# board2.net
KiCad netlist of a schematic drawn in EAGLE
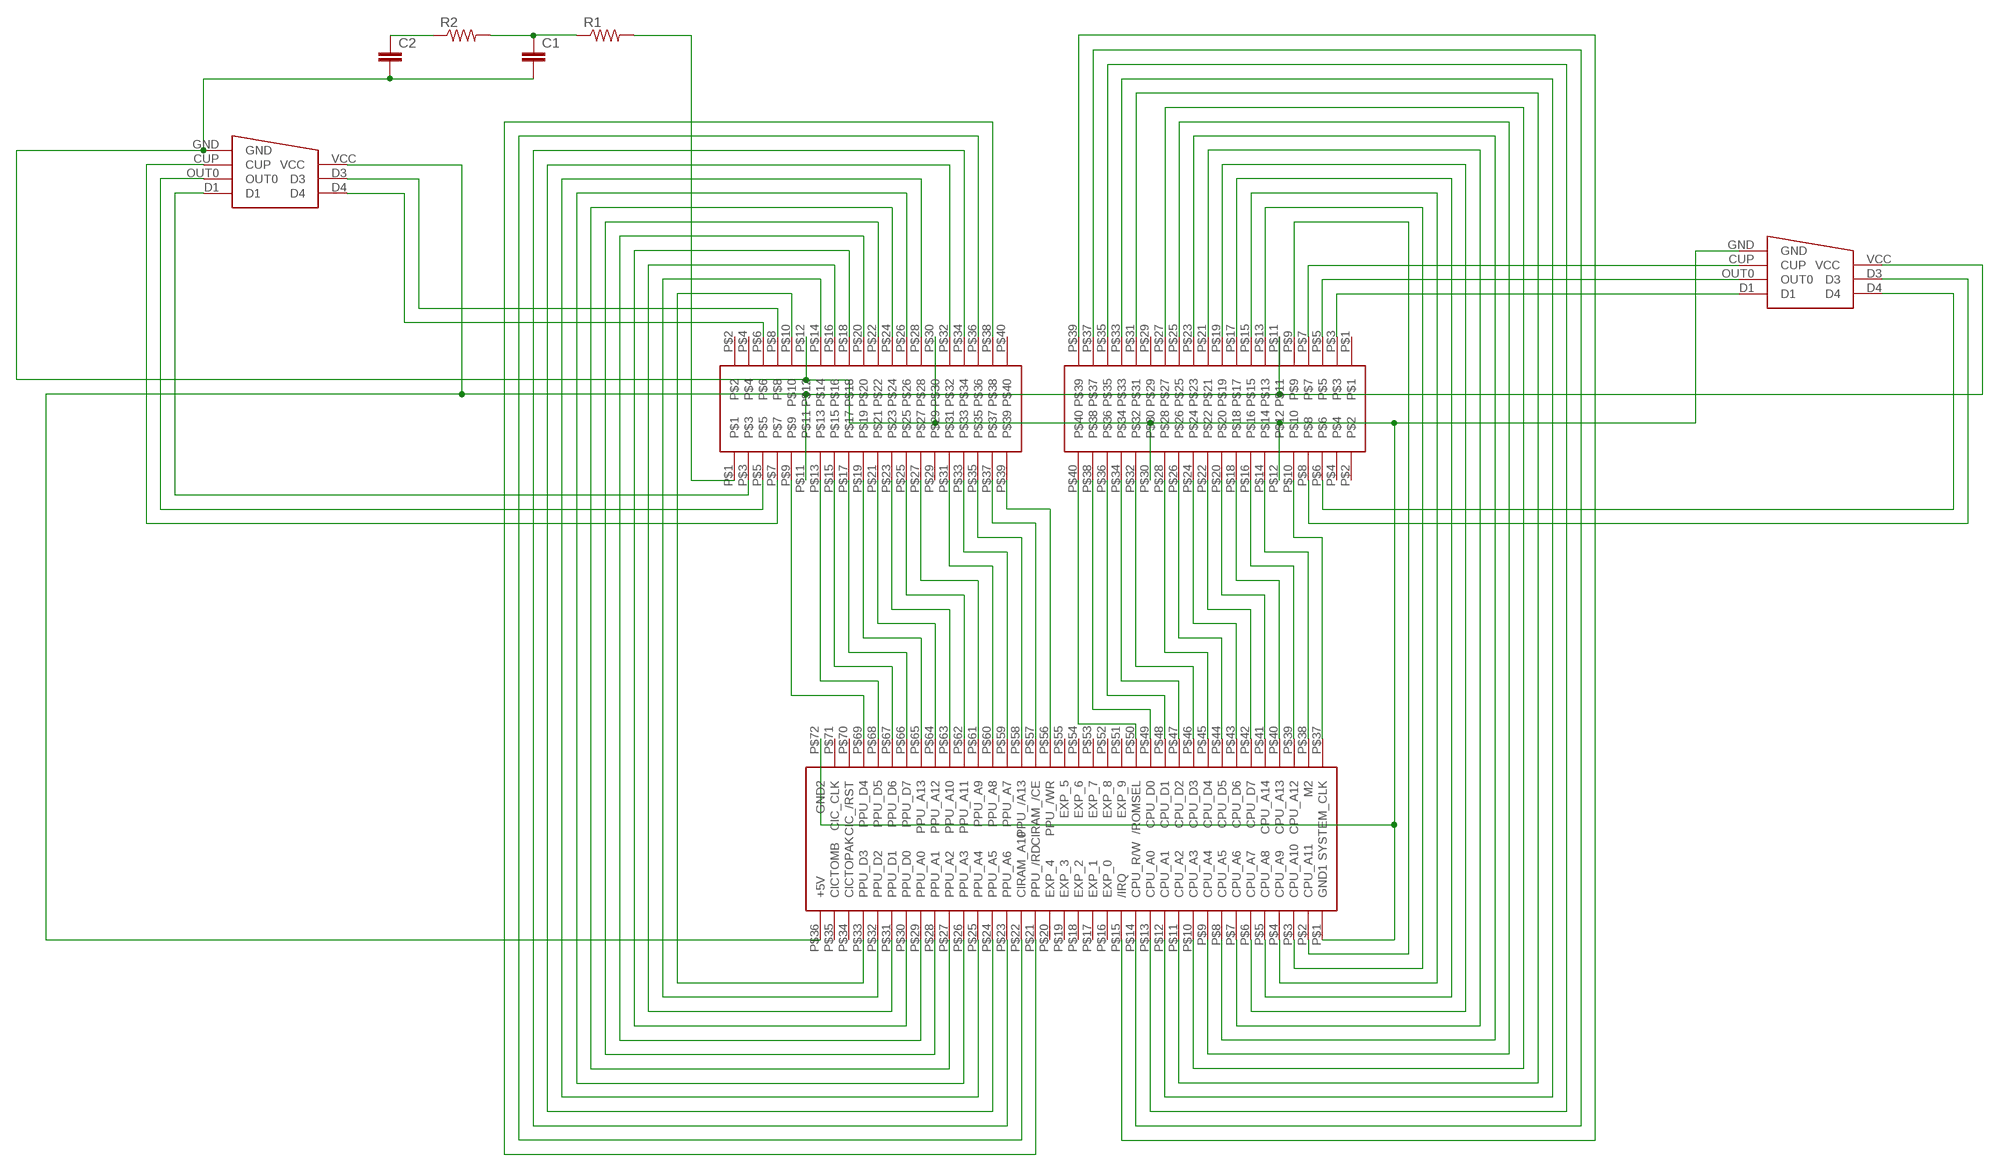
[diagram p0: schematic, sheet 1]

(export (version "E")
  (design (tool "Eeschema 10.0.6"))
  (components
    (comp (ref "C1")
      (value "C5/2.5")
      (footprint "eagle-import:C5B2.5")
      (libsource (lib "eagle-import") (part "C5/2.5"))
    )
    (comp (ref "C2")
      (value "C5/2.5")
      (footprint "eagle-import:C5B2.5")
      (libsource (lib "eagle-import") (part "C5/2.5"))
    )
    (comp (ref "R1")
      (value "R-US_0207/12")
      (footprint "eagle-import:0207_12")
      (libsource (lib "eagle-import") (part "R-US_0207/12"))
    )
    (comp (ref "R2")
      (value "R-US_0207/12")
      (footprint "eagle-import:0207_12")
      (libsource (lib "eagle-import") (part "R-US_0207/12"))
    )
    (comp (ref "U$1")
      (value "NES_CONN")
      (footprint "eagle-import:36X2")
      (libsource (lib "eagle-import") (part "NES_CONN"))
    )
    (comp (ref "U$2")
      (value "40PINNER")
      (footprint "eagle-import:40PINNER")
      (libsource (lib "eagle-import") (part "40PINNER"))
    )
    (comp (ref "U$3")
      (value "40PINNER")
      (footprint "eagle-import:40PINNER")
      (libsource (lib "eagle-import") (part "40PINNER"))
    )
    (comp (ref "U$4")
      (value "7CONN")
      (footprint "eagle-import:7CON")
      (libsource (lib "eagle-import") (part "7CONN"))
    )
    (comp (ref "U$5")
      (value "7CONN")
      (footprint "eagle-import:7CON")
      (libsource (lib "eagle-import") (part "7CONN"))
    )
  )
  (nets
    (net (code "1") (name "Net-(C1-Pad1)") (class "Default")
      (node (ref "C1") (pin "1") (pinfunction "1_1") (pintype "passive"))
      (node (ref "R1") (pin "1") (pinfunction "1_1") (pintype "passive"))
      (node (ref "R2") (pin "2") (pinfunction "2_2") (pintype "passive"))
    )
    (net (code "2") (name "Net-(C2-Pad1)") (class "Default")
      (node (ref "C2") (pin "1") (pinfunction "1_1") (pintype "passive"))
      (node (ref "R2") (pin "1") (pinfunction "1_1") (pintype "passive"))
    )
    (net (code "3") (name "Net-(R1-Pad2)") (class "Default")
      (node (ref "R1") (pin "2") (pinfunction "2_2") (pintype "passive"))
      (node (ref "U$2") (pin "P$1") (pinfunction "P$1_P$1") (pintype "bidirectional"))
    )
    (net (code "4") (name "Net-(U$1-+5V)") (class "Default")
      (node (ref "U$1") (pin "P$36") (pinfunction "+5V_P$36") (pintype "bidirectional"))
      (node (ref "U$2") (pin "P$11") (pinfunction "P$11_P$11") (pintype "bidirectional"))
      (node (ref "U$3") (pin "P$11") (pinfunction "P$11_P$11") (pintype "bidirectional"))
      (node (ref "U$4") (pin "VCC") (pinfunction "VCC_VCC") (pintype "bidirectional"))
      (node (ref "U$5") (pin "VCC") (pinfunction "VCC_VCC") (pintype "bidirectional"))
    )
    (net (code "5") (name "Net-(U$1-CIRAM_A10)") (class "Default")
      (node (ref "U$1") (pin "P$22") (pinfunction "CIRAM_A10_P$22") (pintype "bidirectional"))
      (node (ref "U$2") (pin "P$36") (pinfunction "P$36_P$36") (pintype "bidirectional"))
    )
    (net (code "6") (name "Net-(U$1-CIRAM_{slash}CE)") (class "Default")
      (node (ref "U$1") (pin "P$57") (pinfunction "CIRAM_/CE_P$57") (pintype "bidirectional"))
      (node (ref "U$2") (pin "P$37") (pinfunction "P$37_P$37") (pintype "bidirectional"))
    )
    (net (code "7") (name "Net-(U$1-CPU_A0)") (class "Default")
      (node (ref "U$1") (pin "P$13") (pinfunction "CPU_A0_P$13") (pintype "bidirectional"))
      (node (ref "U$3") (pin "P$35") (pinfunction "P$35_P$35") (pintype "bidirectional"))
    )
    (net (code "8") (name "Net-(U$1-CPU_A1)") (class "Default")
      (node (ref "U$1") (pin "P$12") (pinfunction "CPU_A1_P$12") (pintype "bidirectional"))
      (node (ref "U$3") (pin "P$33") (pinfunction "P$33_P$33") (pintype "bidirectional"))
    )
    (net (code "9") (name "Net-(U$1-CPU_A2)") (class "Default")
      (node (ref "U$1") (pin "P$11") (pinfunction "CPU_A2_P$11") (pintype "bidirectional"))
      (node (ref "U$3") (pin "P$31") (pinfunction "P$31_P$31") (pintype "bidirectional"))
    )
    (net (code "10") (name "Net-(U$1-CPU_A3)") (class "Default")
      (node (ref "U$1") (pin "P$10") (pinfunction "CPU_A3_P$10") (pintype "bidirectional"))
      (node (ref "U$3") (pin "P$27") (pinfunction "P$27_P$27") (pintype "bidirectional"))
    )
    (net (code "11") (name "Net-(U$1-CPU_A4)") (class "Default")
      (node (ref "U$1") (pin "P$9") (pinfunction "CPU_A4_P$9") (pintype "bidirectional"))
      (node (ref "U$3") (pin "P$25") (pinfunction "P$25_P$25") (pintype "bidirectional"))
    )
    (net (code "12") (name "Net-(U$1-CPU_A5)") (class "Default")
      (node (ref "U$1") (pin "P$8") (pinfunction "CPU_A5_P$8") (pintype "bidirectional"))
      (node (ref "U$3") (pin "P$23") (pinfunction "P$23_P$23") (pintype "bidirectional"))
    )
    (net (code "13") (name "Net-(U$1-CPU_A6)") (class "Default")
      (node (ref "U$1") (pin "P$7") (pinfunction "CPU_A6_P$7") (pintype "bidirectional"))
      (node (ref "U$3") (pin "P$21") (pinfunction "P$21_P$21") (pintype "bidirectional"))
    )
    (net (code "14") (name "Net-(U$1-CPU_A7)") (class "Default")
      (node (ref "U$1") (pin "P$6") (pinfunction "CPU_A7_P$6") (pintype "bidirectional"))
      (node (ref "U$3") (pin "P$19") (pinfunction "P$19_P$19") (pintype "bidirectional"))
    )
    (net (code "15") (name "Net-(U$1-CPU_A8)") (class "Default")
      (node (ref "U$1") (pin "P$5") (pinfunction "CPU_A8_P$5") (pintype "bidirectional"))
      (node (ref "U$3") (pin "P$17") (pinfunction "P$17_P$17") (pintype "bidirectional"))
    )
    (net (code "16") (name "Net-(U$1-CPU_A9)") (class "Default")
      (node (ref "U$1") (pin "P$4") (pinfunction "CPU_A9_P$4") (pintype "bidirectional"))
      (node (ref "U$3") (pin "P$15") (pinfunction "P$15_P$15") (pintype "bidirectional"))
    )
    (net (code "17") (name "Net-(U$1-CPU_A10)") (class "Default")
      (node (ref "U$1") (pin "P$3") (pinfunction "CPU_A10_P$3") (pintype "bidirectional"))
      (node (ref "U$3") (pin "P$13") (pinfunction "P$13_P$13") (pintype "bidirectional"))
    )
    (net (code "18") (name "Net-(U$1-CPU_A11)") (class "Default")
      (node (ref "U$1") (pin "P$2") (pinfunction "CPU_A11_P$2") (pintype "bidirectional"))
      (node (ref "U$3") (pin "P$9") (pinfunction "P$9_P$9") (pintype "bidirectional"))
    )
    (net (code "19") (name "Net-(U$1-CPU_A12)") (class "Default")
      (node (ref "U$1") (pin "P$39") (pinfunction "CPU_A12_P$39") (pintype "bidirectional"))
      (node (ref "U$3") (pin "P$16") (pinfunction "P$16_P$16") (pintype "bidirectional"))
    )
    (net (code "20") (name "Net-(U$1-CPU_A13)") (class "Default")
      (node (ref "U$1") (pin "P$40") (pinfunction "CPU_A13_P$40") (pintype "bidirectional"))
      (node (ref "U$3") (pin "P$18") (pinfunction "P$18_P$18") (pintype "bidirectional"))
    )
    (net (code "21") (name "Net-(U$1-CPU_A14)") (class "Default")
      (node (ref "U$1") (pin "P$41") (pinfunction "CPU_A14_P$41") (pintype "bidirectional"))
      (node (ref "U$3") (pin "P$20") (pinfunction "P$20_P$20") (pintype "bidirectional"))
    )
    (net (code "22") (name "Net-(U$1-CPU_D0)") (class "Default")
      (node (ref "U$1") (pin "P$49") (pinfunction "CPU_D0_P$49") (pintype "bidirectional"))
      (node (ref "U$3") (pin "P$38") (pinfunction "P$38_P$38") (pintype "bidirectional"))
    )
    (net (code "23") (name "Net-(U$1-CPU_D1)") (class "Default")
      (node (ref "U$1") (pin "P$48") (pinfunction "CPU_D1_P$48") (pintype "bidirectional"))
      (node (ref "U$3") (pin "P$36") (pinfunction "P$36_P$36") (pintype "bidirectional"))
    )
    (net (code "24") (name "Net-(U$1-CPU_D2)") (class "Default")
      (node (ref "U$1") (pin "P$47") (pinfunction "CPU_D2_P$47") (pintype "bidirectional"))
      (node (ref "U$3") (pin "P$34") (pinfunction "P$34_P$34") (pintype "bidirectional"))
    )
    (net (code "25") (name "Net-(U$1-CPU_D3)") (class "Default")
      (node (ref "U$1") (pin "P$46") (pinfunction "CPU_D3_P$46") (pintype "bidirectional"))
      (node (ref "U$3") (pin "P$32") (pinfunction "P$32_P$32") (pintype "bidirectional"))
    )
    (net (code "26") (name "Net-(U$1-CPU_D4)") (class "Default")
      (node (ref "U$1") (pin "P$45") (pinfunction "CPU_D4_P$45") (pintype "bidirectional"))
      (node (ref "U$3") (pin "P$28") (pinfunction "P$28_P$28") (pintype "bidirectional"))
    )
    (net (code "27") (name "Net-(U$1-CPU_D5)") (class "Default")
      (node (ref "U$1") (pin "P$44") (pinfunction "CPU_D5_P$44") (pintype "bidirectional"))
      (node (ref "U$3") (pin "P$26") (pinfunction "P$26_P$26") (pintype "bidirectional"))
    )
    (net (code "28") (name "Net-(U$1-CPU_D6)") (class "Default")
      (node (ref "U$1") (pin "P$43") (pinfunction "CPU_D6_P$43") (pintype "bidirectional"))
      (node (ref "U$3") (pin "P$24") (pinfunction "P$24_P$24") (pintype "bidirectional"))
    )
    (net (code "29") (name "Net-(U$1-CPU_D7)") (class "Default")
      (node (ref "U$1") (pin "P$42") (pinfunction "CPU_D7_P$42") (pintype "bidirectional"))
      (node (ref "U$3") (pin "P$22") (pinfunction "P$22_P$22") (pintype "bidirectional"))
    )
    (net (code "30") (name "Net-(U$1-CPU_R{slash}W)") (class "Default")
      (node (ref "U$1") (pin "P$14") (pinfunction "CPU_R/W_P$14") (pintype "bidirectional"))
      (node (ref "U$3") (pin "P$37") (pinfunction "P$37_P$37") (pintype "bidirectional"))
    )
    (net (code "31") (name "Net-(U$1-GND1)") (class "Default")
      (node (ref "C1") (pin "2") (pinfunction "2_2") (pintype "passive"))
      (node (ref "C2") (pin "2") (pinfunction "2_2") (pintype "passive"))
      (node (ref "U$1") (pin "P$1") (pinfunction "GND1_P$1") (pintype "bidirectional"))
      (node (ref "U$1") (pin "P$72") (pinfunction "GND2_P$72") (pintype "bidirectional"))
      (node (ref "U$2") (pin "P$12") (pinfunction "P$12_P$12") (pintype "bidirectional"))
      (node (ref "U$2") (pin "P$30") (pinfunction "P$30_P$30") (pintype "bidirectional"))
      (node (ref "U$3") (pin "P$12") (pinfunction "P$12_P$12") (pintype "bidirectional"))
      (node (ref "U$3") (pin "P$30") (pinfunction "P$30_P$30") (pintype "bidirectional"))
      (node (ref "U$4") (pin "GND") (pinfunction "GND_GND") (pintype "bidirectional"))
      (node (ref "U$5") (pin "GND") (pinfunction "GND_GND") (pintype "bidirectional"))
    )
    (net (code "32") (name "Net-(U$1-M2)") (class "Default")
      (node (ref "U$1") (pin "P$38") (pinfunction "M2_P$38") (pintype "bidirectional"))
      (node (ref "U$3") (pin "P$14") (pinfunction "P$14_P$14") (pintype "bidirectional"))
    )
    (net (code "33") (name "Net-(U$1-PPU_A0)") (class "Default")
      (node (ref "U$1") (pin "P$29") (pinfunction "PPU_A0_P$29") (pintype "bidirectional"))
      (node (ref "U$2") (pin "P$20") (pinfunction "P$20_P$20") (pintype "bidirectional"))
    )
    (net (code "34") (name "Net-(U$1-PPU_A1)") (class "Default")
      (node (ref "U$1") (pin "P$28") (pinfunction "PPU_A1_P$28") (pintype "bidirectional"))
      (node (ref "U$2") (pin "P$22") (pinfunction "P$22_P$22") (pintype "bidirectional"))
    )
    (net (code "35") (name "Net-(U$1-PPU_A2)") (class "Default")
      (node (ref "U$1") (pin "P$27") (pinfunction "PPU_A2_P$27") (pintype "bidirectional"))
      (node (ref "U$2") (pin "P$24") (pinfunction "P$24_P$24") (pintype "bidirectional"))
    )
    (net (code "36") (name "Net-(U$1-PPU_A3)") (class "Default")
      (node (ref "U$1") (pin "P$26") (pinfunction "PPU_A3_P$26") (pintype "bidirectional"))
      (node (ref "U$2") (pin "P$26") (pinfunction "P$26_P$26") (pintype "bidirectional"))
    )
    (net (code "37") (name "Net-(U$1-PPU_A4)") (class "Default")
      (node (ref "U$1") (pin "P$25") (pinfunction "PPU_A4_P$25") (pintype "bidirectional"))
      (node (ref "U$2") (pin "P$28") (pinfunction "P$28_P$28") (pintype "bidirectional"))
    )
    (net (code "38") (name "Net-(U$1-PPU_A5)") (class "Default")
      (node (ref "U$1") (pin "P$24") (pinfunction "PPU_A5_P$24") (pintype "bidirectional"))
      (node (ref "U$2") (pin "P$32") (pinfunction "P$32_P$32") (pintype "bidirectional"))
    )
    (net (code "39") (name "Net-(U$1-PPU_A6)") (class "Default")
      (node (ref "U$1") (pin "P$23") (pinfunction "PPU_A6_P$23") (pintype "bidirectional"))
      (node (ref "U$2") (pin "P$34") (pinfunction "P$34_P$34") (pintype "bidirectional"))
    )
    (net (code "40") (name "Net-(U$1-PPU_A7)") (class "Default")
      (node (ref "U$1") (pin "P$59") (pinfunction "PPU_A7_P$59") (pintype "bidirectional"))
      (node (ref "U$2") (pin "P$33") (pinfunction "P$33_P$33") (pintype "bidirectional"))
    )
    (net (code "41") (name "Net-(U$1-PPU_A8)") (class "Default")
      (node (ref "U$1") (pin "P$60") (pinfunction "PPU_A8_P$60") (pintype "bidirectional"))
      (node (ref "U$2") (pin "P$31") (pinfunction "P$31_P$31") (pintype "bidirectional"))
    )
    (net (code "42") (name "Net-(U$1-PPU_A9)") (class "Default")
      (node (ref "U$1") (pin "P$61") (pinfunction "PPU_A9_P$61") (pintype "bidirectional"))
      (node (ref "U$2") (pin "P$27") (pinfunction "P$27_P$27") (pintype "bidirectional"))
    )
    (net (code "43") (name "Net-(U$1-PPU_A10)") (class "Default")
      (node (ref "U$1") (pin "P$63") (pinfunction "PPU_A10_P$63") (pintype "bidirectional"))
      (node (ref "U$2") (pin "P$23") (pinfunction "P$23_P$23") (pintype "bidirectional"))
    )
    (net (code "44") (name "Net-(U$1-PPU_A11)") (class "Default")
      (node (ref "U$1") (pin "P$62") (pinfunction "PPU_A11_P$62") (pintype "bidirectional"))
      (node (ref "U$2") (pin "P$25") (pinfunction "P$25_P$25") (pintype "bidirectional"))
    )
    (net (code "45") (name "Net-(U$1-PPU_A12)") (class "Default")
      (node (ref "U$1") (pin "P$64") (pinfunction "PPU_A12_P$64") (pintype "bidirectional"))
      (node (ref "U$2") (pin "P$21") (pinfunction "P$21_P$21") (pintype "bidirectional"))
    )
    (net (code "46") (name "Net-(U$1-PPU_A13)") (class "Default")
      (node (ref "U$1") (pin "P$65") (pinfunction "PPU_A13_P$65") (pintype "bidirectional"))
      (node (ref "U$2") (pin "P$19") (pinfunction "P$19_P$19") (pintype "bidirectional"))
    )
    (net (code "47") (name "Net-(U$1-PPU_D0)") (class "Default")
      (node (ref "U$1") (pin "P$30") (pinfunction "PPU_D0_P$30") (pintype "bidirectional"))
      (node (ref "U$2") (pin "P$18") (pinfunction "P$18_P$18") (pintype "bidirectional"))
    )
    (net (code "48") (name "Net-(U$1-PPU_D1)") (class "Default")
      (node (ref "U$1") (pin "P$31") (pinfunction "PPU_D1_P$31") (pintype "bidirectional"))
      (node (ref "U$2") (pin "P$16") (pinfunction "P$16_P$16") (pintype "bidirectional"))
    )
    (net (code "49") (name "Net-(U$1-PPU_D2)") (class "Default")
      (node (ref "U$1") (pin "P$32") (pinfunction "PPU_D2_P$32") (pintype "bidirectional"))
      (node (ref "U$2") (pin "P$14") (pinfunction "P$14_P$14") (pintype "bidirectional"))
    )
    (net (code "50") (name "Net-(U$1-PPU_D3)") (class "Default")
      (node (ref "U$1") (pin "P$33") (pinfunction "PPU_D3_P$33") (pintype "bidirectional"))
      (node (ref "U$2") (pin "P$10") (pinfunction "P$10_P$10") (pintype "bidirectional"))
    )
    (net (code "51") (name "Net-(U$1-PPU_D4)") (class "Default")
      (node (ref "U$1") (pin "P$69") (pinfunction "PPU_D4_P$69") (pintype "bidirectional"))
      (node (ref "U$2") (pin "P$9") (pinfunction "P$9_P$9") (pintype "bidirectional"))
    )
    (net (code "52") (name "Net-(U$1-PPU_D5)") (class "Default")
      (node (ref "U$1") (pin "P$68") (pinfunction "PPU_D5_P$68") (pintype "bidirectional"))
      (node (ref "U$2") (pin "P$13") (pinfunction "P$13_P$13") (pintype "bidirectional"))
    )
    (net (code "53") (name "Net-(U$1-PPU_D6)") (class "Default")
      (node (ref "U$1") (pin "P$67") (pinfunction "PPU_D6_P$67") (pintype "bidirectional"))
      (node (ref "U$2") (pin "P$15") (pinfunction "P$15_P$15") (pintype "bidirectional"))
    )
    (net (code "54") (name "Net-(U$1-PPU_D7)") (class "Default")
      (node (ref "U$1") (pin "P$66") (pinfunction "PPU_D7_P$66") (pintype "bidirectional"))
      (node (ref "U$2") (pin "P$17") (pinfunction "P$17_P$17") (pintype "bidirectional"))
    )
    (net (code "55") (name "Net-(U$1-PPU_{slash}A13)") (class "Default")
      (node (ref "U$1") (pin "P$58") (pinfunction "PPU_/A13_P$58") (pintype "bidirectional"))
      (node (ref "U$2") (pin "P$35") (pinfunction "P$35_P$35") (pintype "bidirectional"))
    )
    (net (code "56") (name "Net-(U$1-PPU_{slash}RD)") (class "Default")
      (node (ref "U$1") (pin "P$21") (pinfunction "PPU_/RD_P$21") (pintype "bidirectional"))
      (node (ref "U$2") (pin "P$38") (pinfunction "P$38_P$38") (pintype "bidirectional"))
    )
    (net (code "57") (name "Net-(U$1-PPU_{slash}WR)") (class "Default")
      (node (ref "U$1") (pin "P$56") (pinfunction "PPU_/WR_P$56") (pintype "bidirectional"))
      (node (ref "U$2") (pin "P$39") (pinfunction "P$39_P$39") (pintype "bidirectional"))
    )
    (net (code "58") (name "Net-(U$1-SYSTEM_CLK)") (class "Default")
      (node (ref "U$1") (pin "P$37") (pinfunction "SYSTEM_CLK_P$37") (pintype "bidirectional"))
      (node (ref "U$3") (pin "P$10") (pinfunction "P$10_P$10") (pintype "bidirectional"))
    )
    (net (code "59") (name "Net-(U$1-{slash}IRQ)") (class "Default")
      (node (ref "U$1") (pin "P$15") (pinfunction "/IRQ_P$15") (pintype "bidirectional"))
      (node (ref "U$3") (pin "P$39") (pinfunction "P$39_P$39") (pintype "bidirectional"))
    )
    (net (code "60") (name "Net-(U$1-{slash}ROMSEL)") (class "Default")
      (node (ref "U$1") (pin "P$50") (pinfunction "/ROMSEL_P$50") (pintype "bidirectional"))
      (node (ref "U$3") (pin "P$40") (pinfunction "P$40_P$40") (pintype "bidirectional"))
    )
    (net (code "61") (name "Net-(U$2-PadP$3)") (class "Default")
      (node (ref "U$2") (pin "P$3") (pinfunction "P$3_P$3") (pintype "bidirectional"))
      (node (ref "U$5") (pin "D1") (pinfunction "D1_D1") (pintype "bidirectional"))
    )
    (net (code "62") (name "Net-(U$2-PadP$5)") (class "Default")
      (node (ref "U$2") (pin "P$5") (pinfunction "P$5_P$5") (pintype "bidirectional"))
      (node (ref "U$5") (pin "OUT0") (pinfunction "OUT0_OUT0") (pintype "bidirectional"))
    )
    (net (code "63") (name "Net-(U$2-PadP$6)") (class "Default")
      (node (ref "U$2") (pin "P$6") (pinfunction "P$6_P$6") (pintype "bidirectional"))
      (node (ref "U$5") (pin "D4") (pinfunction "D4_D4") (pintype "bidirectional"))
    )
    (net (code "64") (name "Net-(U$2-PadP$7)") (class "Default")
      (node (ref "U$2") (pin "P$7") (pinfunction "P$7_P$7") (pintype "bidirectional"))
      (node (ref "U$5") (pin "CUP") (pinfunction "CUP_CUP") (pintype "bidirectional"))
    )
    (net (code "65") (name "Net-(U$2-PadP$8)") (class "Default")
      (node (ref "U$2") (pin "P$8") (pinfunction "P$8_P$8") (pintype "bidirectional"))
      (node (ref "U$5") (pin "D3") (pinfunction "D3_D3") (pintype "bidirectional"))
    )
    (net (code "66") (name "Net-(U$3-PadP$3)") (class "Default")
      (node (ref "U$3") (pin "P$3") (pinfunction "P$3_P$3") (pintype "bidirectional"))
      (node (ref "U$4") (pin "D1") (pinfunction "D1_D1") (pintype "bidirectional"))
    )
    (net (code "67") (name "Net-(U$3-PadP$5)") (class "Default")
      (node (ref "U$3") (pin "P$5") (pinfunction "P$5_P$5") (pintype "bidirectional"))
      (node (ref "U$4") (pin "OUT0") (pinfunction "OUT0_OUT0") (pintype "bidirectional"))
    )
    (net (code "68") (name "Net-(U$3-PadP$6)") (class "Default")
      (node (ref "U$3") (pin "P$6") (pinfunction "P$6_P$6") (pintype "bidirectional"))
      (node (ref "U$4") (pin "D4") (pinfunction "D4_D4") (pintype "bidirectional"))
    )
    (net (code "69") (name "Net-(U$3-PadP$7)") (class "Default")
      (node (ref "U$3") (pin "P$7") (pinfunction "P$7_P$7") (pintype "bidirectional"))
      (node (ref "U$4") (pin "CUP") (pinfunction "CUP_CUP") (pintype "bidirectional"))
    )
    (net (code "70") (name "Net-(U$3-PadP$8)") (class "Default")
      (node (ref "U$3") (pin "P$8") (pinfunction "P$8_P$8") (pintype "bidirectional"))
      (node (ref "U$4") (pin "D3") (pinfunction "D3_D3") (pintype "bidirectional"))
    )
    (net (code "71") (name "unconnected-(U$1-CICTOMB-PadP$35)") (class "Default")
      (node (ref "U$1") (pin "P$35") (pinfunction "CICTOMB_P$35") (pintype "bidirectional"))
    )
    (net (code "72") (name "unconnected-(U$1-CICTOPAK-PadP$34)") (class "Default")
      (node (ref "U$1") (pin "P$34") (pinfunction "CICTOPAK_P$34") (pintype "bidirectional"))
    )
    (net (code "73") (name "unconnected-(U$1-CIC_CLK-PadP$71)") (class "Default")
      (node (ref "U$1") (pin "P$71") (pinfunction "CIC_CLK_P$71") (pintype "bidirectional"))
    )
    (net (code "74") (name "unconnected-(U$1-CIC_{slash}RST-PadP$70)") (class "Default")
      (node (ref "U$1") (pin "P$70") (pinfunction "CIC_/RST_P$70") (pintype "bidirectional"))
    )
    (net (code "75") (name "unconnected-(U$1-EXP_0-PadP$16)") (class "Default")
      (node (ref "U$1") (pin "P$16") (pinfunction "EXP_0_P$16") (pintype "bidirectional"))
    )
    (net (code "76") (name "unconnected-(U$1-EXP_1-PadP$17)") (class "Default")
      (node (ref "U$1") (pin "P$17") (pinfunction "EXP_1_P$17") (pintype "bidirectional"))
    )
    (net (code "77") (name "unconnected-(U$1-EXP_2-PadP$18)") (class "Default")
      (node (ref "U$1") (pin "P$18") (pinfunction "EXP_2_P$18") (pintype "bidirectional"))
    )
    (net (code "78") (name "unconnected-(U$1-EXP_3-PadP$19)") (class "Default")
      (node (ref "U$1") (pin "P$19") (pinfunction "EXP_3_P$19") (pintype "bidirectional"))
    )
    (net (code "79") (name "unconnected-(U$1-EXP_4-PadP$20)") (class "Default")
      (node (ref "U$1") (pin "P$20") (pinfunction "EXP_4_P$20") (pintype "bidirectional"))
    )
    (net (code "80") (name "unconnected-(U$1-EXP_5-PadP$55)") (class "Default")
      (node (ref "U$1") (pin "P$55") (pinfunction "EXP_5_P$55") (pintype "bidirectional"))
    )
    (net (code "81") (name "unconnected-(U$1-EXP_6-PadP$54)") (class "Default")
      (node (ref "U$1") (pin "P$54") (pinfunction "EXP_6_P$54") (pintype "bidirectional"))
    )
    (net (code "82") (name "unconnected-(U$1-EXP_7-PadP$53)") (class "Default")
      (node (ref "U$1") (pin "P$53") (pinfunction "EXP_7_P$53") (pintype "bidirectional"))
    )
    (net (code "83") (name "unconnected-(U$1-EXP_8-PadP$52)") (class "Default")
      (node (ref "U$1") (pin "P$52") (pinfunction "EXP_8_P$52") (pintype "bidirectional"))
    )
    (net (code "84") (name "unconnected-(U$1-EXP_9-PadP$51)") (class "Default")
      (node (ref "U$1") (pin "P$51") (pinfunction "EXP_9_P$51") (pintype "bidirectional"))
    )
    (net (code "85") (name "unconnected-(U$2-PadP$2)") (class "Default")
      (node (ref "U$2") (pin "P$2") (pinfunction "P$2_P$2") (pintype "bidirectional"))
    )
    (net (code "86") (name "unconnected-(U$2-PadP$4)") (class "Default")
      (node (ref "U$2") (pin "P$4") (pinfunction "P$4_P$4") (pintype "bidirectional"))
    )
    (net (code "87") (name "unconnected-(U$2-PadP$29)") (class "Default")
      (node (ref "U$2") (pin "P$29") (pinfunction "P$29_P$29") (pintype "bidirectional"))
    )
    (net (code "88") (name "unconnected-(U$2-PadP$40)") (class "Default")
      (node (ref "U$2") (pin "P$40") (pinfunction "P$40_P$40") (pintype "bidirectional"))
    )
    (net (code "89") (name "unconnected-(U$3-PadP$1)") (class "Default")
      (node (ref "U$3") (pin "P$1") (pinfunction "P$1_P$1") (pintype "bidirectional"))
    )
    (net (code "90") (name "unconnected-(U$3-PadP$2)") (class "Default")
      (node (ref "U$3") (pin "P$2") (pinfunction "P$2_P$2") (pintype "bidirectional"))
    )
    (net (code "91") (name "unconnected-(U$3-PadP$4)") (class "Default")
      (node (ref "U$3") (pin "P$4") (pinfunction "P$4_P$4") (pintype "bidirectional"))
    )
    (net (code "92") (name "unconnected-(U$3-PadP$29)") (class "Default")
      (node (ref "U$3") (pin "P$29") (pinfunction "P$29_P$29") (pintype "bidirectional"))
    )
  )
)
